# 51.net
KiCad netlist of a schematic drawn in Altium Designer
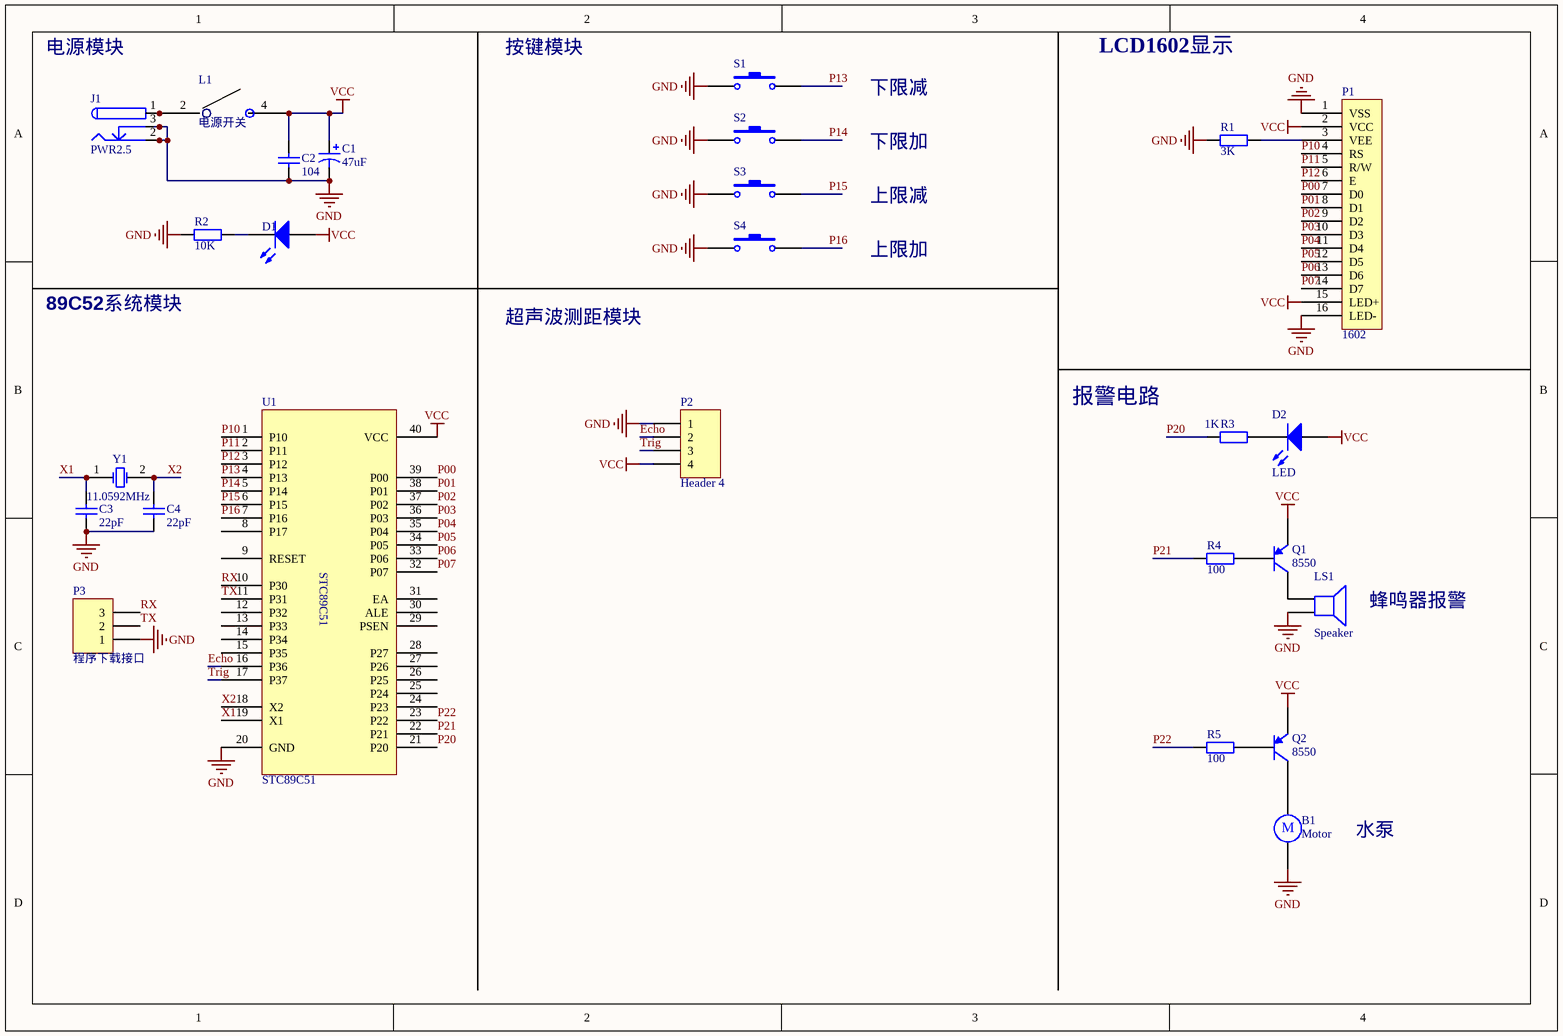
[diagram p0: 基于51单片机超声波测距系统.SchDoc]

(export (version "E")
  (design (tool "Eeschema 10.0.6"))
  (components
    (comp (ref "B1")
      (value "Motor")
      (footprint "2p座")
      (description "Motor, General Kind")
      (fields (field (name "PUBLISHER") "Altium Limited"))
      (libsource (lib "Miscellaneous Devices") (part "Motor"))
    )
    (comp (ref "C1")
      (value "47uF")
      (footprint "电解电容")
      (description "Polarized Capacitor (Radial)")
      (fields (field (name "PUBLISHER") "Altium Limited"))
      (libsource (lib "Miscellaneous Devices") (part "Cap Pol1"))
    )
    (comp (ref "C2")
      (value "104")
      (footprint "瓷片电容")
      (description "Capacitor")
      (fields (field (name "PUBLISHER") "Altium Limited"))
      (libsource (lib "Miscellaneous Devices") (part "Cap"))
    )
    (comp (ref "C3")
      (value "22pF")
      (footprint "瓷片电容")
      (description "Capacitor")
      (fields (field (name "PUBLISHER") "Altium Limited"))
      (libsource (lib "Miscellaneous Devices") (part "Cap"))
    )
    (comp (ref "C4")
      (value "22pF")
      (footprint "瓷片电容")
      (description "Capacitor")
      (fields (field (name "PUBLISHER") "Altium Limited"))
      (libsource (lib "Miscellaneous Devices") (part "Cap"))
    )
    (comp (ref "D1")
      (value "LED")
      (footprint "发光二极管")
      (description "Typical INFRARED GaAs LED")
      (fields (field (name "PUBLISHER") "Altium Limited"))
      (libsource (lib "Miscellaneous Devices") (part "LED0"))
    )
    (comp (ref "D2")
      (value "LED")
      (footprint "发光二极管")
      (description "Typical INFRARED GaAs LED")
      (fields (field (name "PUBLISHER") "Altium Limited"))
      (libsource (lib "Miscellaneous Devices") (part "LED0"))
    )
    (comp (ref "J1")
      (value "PWR2.5")
      (footprint "电源接头")
      (description "Low Voltage Power Supply Connector")
      (fields (field (name "PUBLISHER") "Altium Limited"))
      (libsource (lib "Miscellaneous Connectors") (part "PWR2.5"))
    )
    (comp (ref "L1") (value "电源开关") (footprint "开关") (libsource (lib "元件原理图") (part "Liujiao")))
    (comp (ref "LS1")
      (value "Speaker")
      (footprint "蜂鸣器")
      (description "Loudspeaker")
      (fields (field (name "PUBLISHER") "Altium Limited"))
      (libsource (lib "Miscellaneous Devices") (part "Speaker"))
    )
    (comp (ref "P1") (value "1602") (footprint "LCD1602液晶") (libsource (lib "元件原理图") (part "1602")))
    (comp (ref "P2")
      (value "Header 4")
      (footprint "4P座")
      (description "Header, 4-Pin")
      (fields (field (name "PUBLISHER") "Altium Limited"))
      (libsource (lib "Miscellaneous Connectors") (part "Header 4"))
    )
    (comp (ref "P3")
      (value "程序下载接口")
      (footprint "下载器")
      (description "Header, 3-Pin")
      (fields (field (name "PUBLISHER") "Altium Limited"))
      (libsource (lib "Miscellaneous Connectors") (part "Header 3"))
    )
    (comp (ref "Q1")
      (value "8550")
      (footprint "三极管")
      (description "PNP General Purpose Amplifier")
      (fields (field (name "PUBLISHER") "Altium Limited"))
      (libsource (lib "Miscellaneous Devices") (part "2N3906"))
    )
    (comp (ref "Q2")
      (value "8550")
      (footprint "三极管")
      (description "PNP General Purpose Amplifier")
      (fields (field (name "PUBLISHER") "Altium Limited"))
      (libsource (lib "Miscellaneous Devices") (part "2N3906"))
    )
    (comp (ref "R1")
      (value "3K")
      (footprint "电阻")
      (description "Resistor")
      (fields (field (name "PUBLISHER") "Altium Limited"))
      (libsource (lib "Miscellaneous Devices") (part "Res2"))
    )
    (comp (ref "R2")
      (value "10K")
      (footprint "电阻")
      (description "Resistor")
      (fields (field (name "PUBLISHER") "Altium Limited"))
      (libsource (lib "Miscellaneous Devices") (part "Res2"))
    )
    (comp (ref "R3")
      (value "1K")
      (footprint "电阻")
      (description "Resistor")
      (fields (field (name "PUBLISHER") "Altium Limited"))
      (libsource (lib "Miscellaneous Devices") (part "Res2"))
    )
    (comp (ref "R4")
      (value "100")
      (footprint "电阻")
      (description "Resistor")
      (fields (field (name "PUBLISHER") "Altium Limited"))
      (libsource (lib "Miscellaneous Devices") (part "Res2"))
    )
    (comp (ref "R5")
      (value "100")
      (footprint "电阻")
      (description "Resistor")
      (fields (field (name "PUBLISHER") "Altium Limited"))
      (libsource (lib "Miscellaneous Devices") (part "Res2"))
    )
    (comp (ref "S1")
      (value "~")
      (footprint "按键")
      (description "Switch")
      (fields (field (name "PUBLISHER") "Altium Limited"))
      (libsource (lib "Miscellaneous Devices") (part "SW-PB"))
    )
    (comp (ref "S2")
      (value "~")
      (footprint "按键")
      (description "Switch")
      (fields (field (name "PUBLISHER") "Altium Limited"))
      (libsource (lib "Miscellaneous Devices") (part "SW-PB"))
    )
    (comp (ref "S3")
      (value "~")
      (footprint "按键")
      (description "Switch")
      (fields (field (name "PUBLISHER") "Altium Limited"))
      (libsource (lib "Miscellaneous Devices") (part "SW-PB"))
    )
    (comp (ref "S4")
      (value "~")
      (footprint "按键")
      (description "Switch")
      (fields (field (name "PUBLISHER") "Altium Limited"))
      (libsource (lib "Miscellaneous Devices") (part "SW-PB"))
    )
    (comp (ref "U1") (value "STC89C51") (footprint "51单片机") (libsource (lib "元件原理图") (part "STC89C52")))
    (comp (ref "Y1")
      (value "11.0592MHz")
      (footprint "晶振")
      (description "Crystal Oscillator")
      (fields (field (name "PUBLISHER") "Altium Limited"))
      (libsource (lib "Miscellaneous Devices") (part "XTAL"))
    )
  )
  (nets
    (net (code "1") (name "/Echo") (class "Default")
      (node (ref "P2") (pin "2") (pinfunction "2_2") (pintype "passive"))
      (node (ref "U1") (pin "16") (pinfunction "P36_16") (pintype "passive"))
    )
    (net (code "2") (name "/P00") (class "Default")
      (node (ref "P1") (pin "7") (pinfunction "D0_7") (pintype "passive"))
      (node (ref "U1") (pin "39") (pinfunction "P00_39") (pintype "passive"))
    )
    (net (code "3") (name "/P01") (class "Default")
      (node (ref "P1") (pin "8") (pinfunction "D1_8") (pintype "passive"))
      (node (ref "U1") (pin "38") (pinfunction "P01_38") (pintype "passive"))
    )
    (net (code "4") (name "/P02") (class "Default")
      (node (ref "P1") (pin "9") (pinfunction "D2_9") (pintype "passive"))
      (node (ref "U1") (pin "37") (pinfunction "P02_37") (pintype "passive"))
    )
    (net (code "5") (name "/P03") (class "Default")
      (node (ref "P1") (pin "10") (pinfunction "D3_10") (pintype "passive"))
      (node (ref "U1") (pin "36") (pinfunction "P03_36") (pintype "passive"))
    )
    (net (code "6") (name "/P04") (class "Default")
      (node (ref "P1") (pin "11") (pinfunction "D4_11") (pintype "passive"))
      (node (ref "U1") (pin "35") (pinfunction "P04_35") (pintype "passive"))
    )
    (net (code "7") (name "/P05") (class "Default")
      (node (ref "P1") (pin "12") (pinfunction "D5_12") (pintype "passive"))
      (node (ref "U1") (pin "34") (pinfunction "P05_34") (pintype "passive"))
    )
    (net (code "8") (name "/P06") (class "Default")
      (node (ref "P1") (pin "13") (pinfunction "D6_13") (pintype "passive"))
      (node (ref "U1") (pin "33") (pinfunction "P06_33") (pintype "passive"))
    )
    (net (code "9") (name "/P07") (class "Default")
      (node (ref "P1") (pin "14") (pinfunction "D7_14") (pintype "passive"))
      (node (ref "U1") (pin "32") (pinfunction "P07_32") (pintype "passive"))
    )
    (net (code "10") (name "/P10") (class "Default")
      (node (ref "P1") (pin "4") (pinfunction "RS_4") (pintype "passive"))
      (node (ref "U1") (pin "1") (pinfunction "P10_1") (pintype "passive"))
    )
    (net (code "11") (name "/P11") (class "Default")
      (node (ref "P1") (pin "5") (pinfunction "R/W_5") (pintype "passive"))
      (node (ref "U1") (pin "2") (pinfunction "P11_2") (pintype "passive"))
    )
    (net (code "12") (name "/P12") (class "Default")
      (node (ref "P1") (pin "6") (pinfunction "E_6") (pintype "passive"))
      (node (ref "U1") (pin "3") (pinfunction "P12_3") (pintype "passive"))
    )
    (net (code "13") (name "/P13") (class "Default")
      (node (ref "S1") (pin "2") (pinfunction "2_2") (pintype "passive"))
      (node (ref "U1") (pin "4") (pinfunction "P13_4") (pintype "passive"))
    )
    (net (code "14") (name "/P14") (class "Default")
      (node (ref "S2") (pin "2") (pinfunction "2_2") (pintype "passive"))
      (node (ref "U1") (pin "5") (pinfunction "P14_5") (pintype "passive"))
    )
    (net (code "15") (name "/P15") (class "Default")
      (node (ref "S3") (pin "2") (pinfunction "2_2") (pintype "passive"))
      (node (ref "U1") (pin "6") (pinfunction "P15_6") (pintype "passive"))
    )
    (net (code "16") (name "/P16") (class "Default")
      (node (ref "S4") (pin "2") (pinfunction "2_2") (pintype "passive"))
      (node (ref "U1") (pin "7") (pinfunction "P16_7") (pintype "passive"))
    )
    (net (code "17") (name "/P20") (class "Default")
      (node (ref "R3") (pin "1") (pinfunction "1_1") (pintype "passive"))
      (node (ref "U1") (pin "21") (pinfunction "P20_21") (pintype "passive"))
    )
    (net (code "18") (name "/P21") (class "Default")
      (node (ref "R4") (pin "1") (pinfunction "1_1") (pintype "passive"))
      (node (ref "U1") (pin "22") (pinfunction "P21_22") (pintype "passive"))
    )
    (net (code "19") (name "/P22") (class "Default")
      (node (ref "R5") (pin "1") (pinfunction "1_1") (pintype "passive"))
      (node (ref "U1") (pin "23") (pinfunction "P22_23") (pintype "passive"))
    )
    (net (code "20") (name "/RX") (class "Default")
      (node (ref "P3") (pin "3") (pinfunction "3_3") (pintype "passive"))
      (node (ref "U1") (pin "10") (pinfunction "P30_10") (pintype "passive"))
    )
    (net (code "21") (name "/TX") (class "Default")
      (node (ref "P3") (pin "2") (pinfunction "2_2") (pintype "passive"))
      (node (ref "U1") (pin "11") (pinfunction "P31_11") (pintype "passive"))
    )
    (net (code "22") (name "/Trig") (class "Default")
      (node (ref "P2") (pin "3") (pinfunction "3_3") (pintype "passive"))
      (node (ref "U1") (pin "17") (pinfunction "P37_17") (pintype "passive"))
    )
    (net (code "23") (name "/X1") (class "Default")
      (node (ref "C3") (pin "2") (pinfunction "2_2") (pintype "passive"))
      (node (ref "U1") (pin "19") (pinfunction "X1_19") (pintype "passive"))
      (node (ref "Y1") (pin "1") (pinfunction "OSC1_1") (pintype "passive"))
    )
    (net (code "24") (name "/X2") (class "Default")
      (node (ref "C4") (pin "2") (pinfunction "2_2") (pintype "passive"))
      (node (ref "U1") (pin "18") (pinfunction "X2_18") (pintype "passive"))
      (node (ref "Y1") (pin "2") (pinfunction "OSC2_2") (pintype "passive"))
    )
    (net (code "25") (name "GND") (class "Default")
      (node (ref "B1") (pin "2") (pinfunction "2_2") (pintype "passive"))
      (node (ref "C1") (pin "2") (pinfunction "2_2") (pintype "passive"))
      (node (ref "C2") (pin "1") (pinfunction "1_1") (pintype "passive"))
      (node (ref "C3") (pin "1") (pinfunction "1_1") (pintype "passive"))
      (node (ref "C4") (pin "1") (pinfunction "1_1") (pintype "passive"))
      (node (ref "J1") (pin "2") (pinfunction "2_2") (pintype "power_in"))
      (node (ref "J1") (pin "2A") (pinfunction "2A_2A") (pintype "power_in"))
      (node (ref "J1") (pin "2B") (pinfunction "2B_2B") (pintype "power_in"))
      (node (ref "J1") (pin "3") (pinfunction "3_3") (pintype "power_in"))
      (node (ref "J1") (pin "3A") (pinfunction "3A_3A") (pintype "power_in"))
      (node (ref "J1") (pin "3B") (pinfunction "3B_3B") (pintype "power_in"))
      (node (ref "LS1") (pin "2") (pinfunction "2_2") (pintype "passive"))
      (node (ref "P1") (pin "1") (pinfunction "VSS_1") (pintype "passive"))
      (node (ref "P1") (pin "16") (pinfunction "LED-_16") (pintype "passive"))
      (node (ref "P2") (pin "1") (pinfunction "1_1") (pintype "passive"))
      (node (ref "P3") (pin "1") (pinfunction "1_1") (pintype "passive"))
      (node (ref "R1") (pin "1") (pinfunction "1_1") (pintype "passive"))
      (node (ref "R2") (pin "1") (pinfunction "1_1") (pintype "passive"))
      (node (ref "S1") (pin "1") (pinfunction "1_1") (pintype "passive"))
      (node (ref "S2") (pin "1") (pinfunction "1_1") (pintype "passive"))
      (node (ref "S3") (pin "1") (pinfunction "1_1") (pintype "passive"))
      (node (ref "S4") (pin "1") (pinfunction "1_1") (pintype "passive"))
      (node (ref "U1") (pin "20") (pinfunction "GND_20") (pintype "passive"))
    )
    (net (code "26") (name "Net-(D1-K)") (class "Default")
      (node (ref "D1") (pin "2") (pinfunction "K_2") (pintype "passive"))
      (node (ref "R2") (pin "2") (pinfunction "2_2") (pintype "passive"))
    )
    (net (code "27") (name "Net-(D2-K)") (class "Default")
      (node (ref "D2") (pin "2") (pinfunction "K_2") (pintype "passive"))
      (node (ref "R3") (pin "2") (pinfunction "2_2") (pintype "passive"))
    )
    (net (code "28") (name "Net-(L1-1)") (class "Default")
      (node (ref "J1") (pin "1") (pinfunction "1_1") (pintype "power_in"))
      (node (ref "J1") (pin "1A") (pinfunction "1A_1A") (pintype "power_in"))
      (node (ref "J1") (pin "1B") (pinfunction "1B_1B") (pintype "power_in"))
      (node (ref "L1") (pin "2") (pinfunction "1_2") (pintype "passive"))
    )
    (net (code "29") (name "Net-(P1-VEE)") (class "Default")
      (node (ref "P1") (pin "3") (pinfunction "VEE_3") (pintype "passive"))
      (node (ref "R1") (pin "2") (pinfunction "2_2") (pintype "passive"))
    )
    (net (code "30") (name "Net-(Q1-B)") (class "Default")
      (node (ref "Q1") (pin "2") (pinfunction "B_2") (pintype "passive"))
      (node (ref "R4") (pin "2") (pinfunction "2_2") (pintype "passive"))
    )
    (net (code "31") (name "Net-(Q1-C)") (class "Default")
      (node (ref "LS1") (pin "1") (pinfunction "1_1") (pintype "passive"))
      (node (ref "Q1") (pin "3") (pinfunction "C_3") (pintype "passive"))
    )
    (net (code "32") (name "Net-(Q2-B)") (class "Default")
      (node (ref "Q2") (pin "2") (pinfunction "B_2") (pintype "passive"))
      (node (ref "R5") (pin "2") (pinfunction "2_2") (pintype "passive"))
    )
    (net (code "33") (name "Net-(Q2-C)") (class "Default")
      (node (ref "B1") (pin "1") (pinfunction "1_1") (pintype "passive"))
      (node (ref "Q2") (pin "3") (pinfunction "C_3") (pintype "passive"))
    )
    (net (code "34") (name "VCC") (class "Default")
      (node (ref "C1") (pin "1") (pinfunction "1_1") (pintype "passive"))
      (node (ref "C2") (pin "2") (pinfunction "2_2") (pintype "passive"))
      (node (ref "D1") (pin "1") (pinfunction "A_1") (pintype "passive"))
      (node (ref "D2") (pin "1") (pinfunction "A_1") (pintype "passive"))
      (node (ref "L1") (pin "4") (pinfunction "0_4") (pintype "passive"))
      (node (ref "P1") (pin "15") (pinfunction "LED+_15") (pintype "passive"))
      (node (ref "P1") (pin "2") (pinfunction "VCC_2") (pintype "passive"))
      (node (ref "P2") (pin "4") (pinfunction "4_4") (pintype "passive"))
      (node (ref "Q1") (pin "1") (pinfunction "E_1") (pintype "passive"))
      (node (ref "Q2") (pin "1") (pinfunction "E_1") (pintype "passive"))
      (node (ref "U1") (pin "40") (pinfunction "VCC_40") (pintype "passive"))
    )
    (net (code "35") (name "unconnected-(U1-ALE-Pad30)") (class "Default")
      (node (ref "U1") (pin "30") (pinfunction "ALE_30") (pintype "passive"))
    )
    (net (code "36") (name "unconnected-(U1-EA-Pad31)") (class "Default")
      (node (ref "U1") (pin "31") (pinfunction "EA_31") (pintype "passive"))
    )
    (net (code "37") (name "unconnected-(U1-P17-Pad8)") (class "Default")
      (node (ref "U1") (pin "8") (pinfunction "P17_8") (pintype "passive"))
    )
    (net (code "38") (name "unconnected-(U1-P23-Pad24)") (class "Default")
      (node (ref "U1") (pin "24") (pinfunction "P23_24") (pintype "passive"))
    )
    (net (code "39") (name "unconnected-(U1-P24-Pad25)") (class "Default")
      (node (ref "U1") (pin "25") (pinfunction "P24_25") (pintype "passive"))
    )
    (net (code "40") (name "unconnected-(U1-P25-Pad26)") (class "Default")
      (node (ref "U1") (pin "26") (pinfunction "P25_26") (pintype "passive"))
    )
    (net (code "41") (name "unconnected-(U1-P26-Pad27)") (class "Default")
      (node (ref "U1") (pin "27") (pinfunction "P26_27") (pintype "passive"))
    )
    (net (code "42") (name "unconnected-(U1-P27-Pad28)") (class "Default")
      (node (ref "U1") (pin "28") (pinfunction "P27_28") (pintype "passive"))
    )
    (net (code "43") (name "unconnected-(U1-P32-Pad12)") (class "Default")
      (node (ref "U1") (pin "12") (pinfunction "P32_12") (pintype "passive"))
    )
    (net (code "44") (name "unconnected-(U1-P33-Pad13)") (class "Default")
      (node (ref "U1") (pin "13") (pinfunction "P33_13") (pintype "passive"))
    )
    (net (code "45") (name "unconnected-(U1-P34-Pad14)") (class "Default")
      (node (ref "U1") (pin "14") (pinfunction "P34_14") (pintype "passive"))
    )
    (net (code "46") (name "unconnected-(U1-P35-Pad15)") (class "Default")
      (node (ref "U1") (pin "15") (pinfunction "P35_15") (pintype "passive"))
    )
    (net (code "47") (name "unconnected-(U1-PSEN-Pad29)") (class "Default")
      (node (ref "U1") (pin "29") (pinfunction "PSEN_29") (pintype "passive"))
    )
    (net (code "48") (name "unconnected-(U1-RESET-Pad9)") (class "Default")
      (node (ref "U1") (pin "9") (pinfunction "RESET_9") (pintype "passive"))
    )
  )
)
